# RecordStatusShield.net
KiCad netlist of a schematic drawn in EAGLE
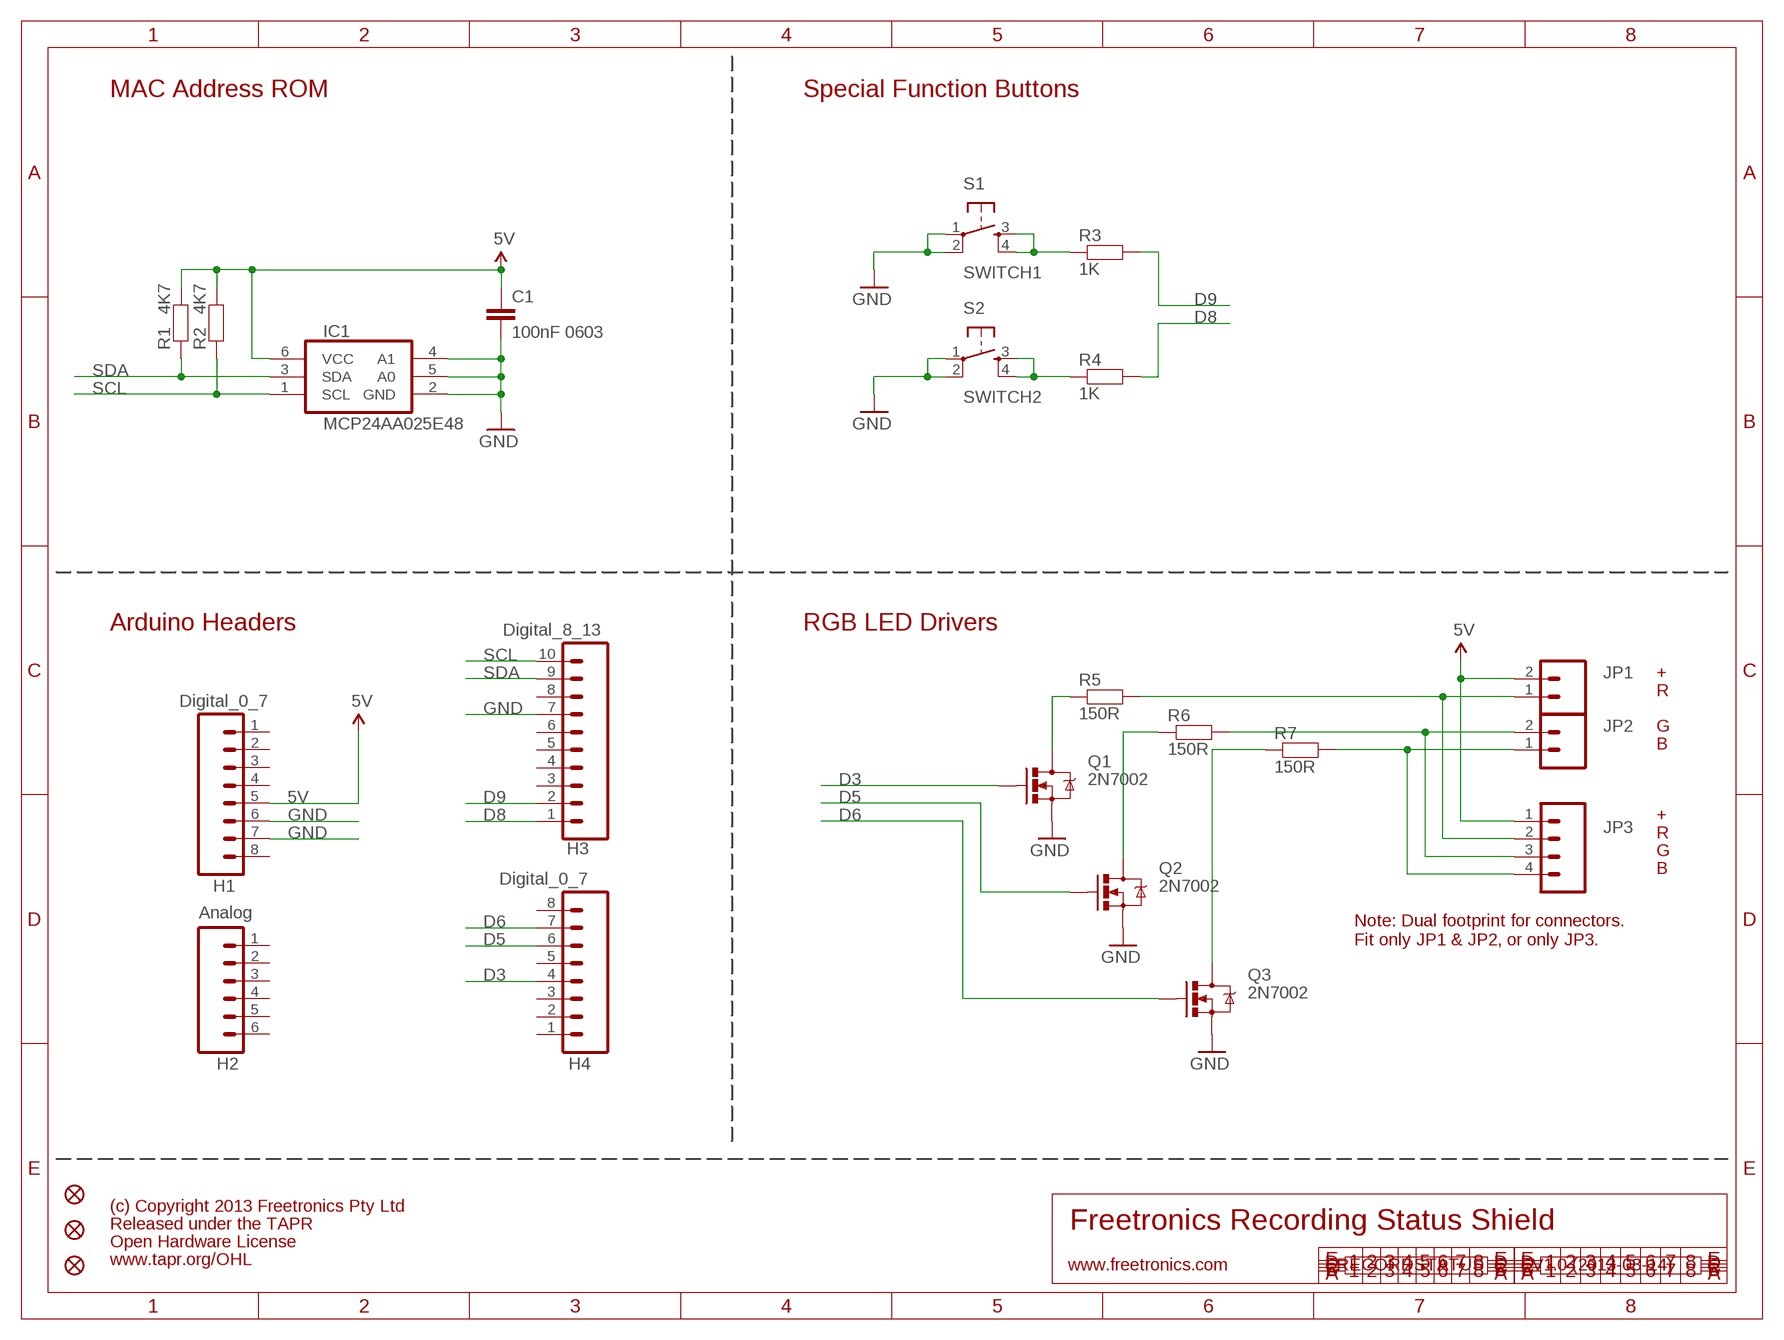
[diagram p0: schematic, sheet 1]

(export (version "E")
  (design (tool "Eeschema 10.0.6"))
  (components
    (comp (ref "C1")
      (value "100nF 0603")
      (footprint "eagle-import:C0603")
      (libsource (lib "eagle-import") (part "C-EUC0603"))
    )
    (comp (ref "FID5")
      (value "FIDUCIAL1X2.5")
      (footprint "eagle-import:FIDUCIAL-1X2.5")
      (libsource (lib "eagle-import") (part "FIDUCIAL1X2.5"))
    )
    (comp (ref "FID6")
      (value "FIDUCIAL1X2.5")
      (footprint "eagle-import:FIDUCIAL-1X2.5")
      (libsource (lib "eagle-import") (part "FIDUCIAL1X2.5"))
    )
    (comp (ref "FID7")
      (value "FIDUCIAL1X2.5")
      (footprint "eagle-import:FIDUCIAL-1X2.5")
      (libsource (lib "eagle-import") (part "FIDUCIAL1X2.5"))
    )
    (comp (ref "H1")
      (value "Digital_0_7")
      (footprint "eagle-import:1X08")
      (libsource (lib "eagle-import") (part "M08"))
    )
    (comp (ref "H2")
      (value "Analog")
      (footprint "eagle-import:1X06")
      (libsource (lib "eagle-import") (part "M06SIP"))
    )
    (comp (ref "H3")
      (value "Digital_8_13")
      (footprint "eagle-import:1X10")
      (libsource (lib "eagle-import") (part "M100.1"))
    )
    (comp (ref "H4")
      (value "Digital_0_7")
      (footprint "eagle-import:1X08")
      (libsource (lib "eagle-import") (part "M08"))
    )
    (comp (ref "IC1")
      (value "MCP24AA025E48")
      (footprint "eagle-import:SOT23-6")
      (libsource (lib "eagle-import") (part "MCP24AA025E48"))
    )
    (comp (ref "JP1")
      (value "M025MM")
      (footprint "eagle-import:SCREWTERMINAL-5MM-2")
      (libsource (lib "eagle-import") (part "M025MM"))
    )
    (comp (ref "JP2")
      (value "M025MM")
      (footprint "eagle-import:SCREWTERMINAL-5MM-2")
      (libsource (lib "eagle-import") (part "M025MM"))
    )
    (comp (ref "JP3")
      (value "M04PTH")
      (footprint "eagle-import:1X04")
      (libsource (lib "eagle-import") (part "M04PTH"))
    )
    (comp (ref "Q1")
      (value "2N7002")
      (footprint "eagle-import:SOT23-3")
      (libsource (lib "eagle-import") (part "MOSFET-NCHANNELSMD"))
    )
    (comp (ref "Q2")
      (value "2N7002")
      (footprint "eagle-import:SOT23-3")
      (libsource (lib "eagle-import") (part "MOSFET-NCHANNELSMD"))
    )
    (comp (ref "Q3")
      (value "2N7002")
      (footprint "eagle-import:SOT23-3")
      (libsource (lib "eagle-import") (part "MOSFET-NCHANNELSMD"))
    )
    (comp (ref "R1")
      (value "4K7")
      (footprint "eagle-import:0603")
      (libsource (lib "eagle-import") (part "RESISTOR0603"))
    )
    (comp (ref "R2")
      (value "4K7")
      (footprint "eagle-import:0603")
      (libsource (lib "eagle-import") (part "RESISTOR0603"))
    )
    (comp (ref "R3")
      (value "1K")
      (footprint "eagle-import:0603")
      (libsource (lib "eagle-import") (part "RESISTOR0603"))
    )
    (comp (ref "R4")
      (value "1K")
      (footprint "eagle-import:0603")
      (libsource (lib "eagle-import") (part "RESISTOR0603"))
    )
    (comp (ref "R5")
      (value "150R")
      (footprint "eagle-import:0603")
      (libsource (lib "eagle-import") (part "RESISTOR0603"))
    )
    (comp (ref "R6")
      (value "150R")
      (footprint "eagle-import:0603")
      (libsource (lib "eagle-import") (part "RESISTOR0603"))
    )
    (comp (ref "R7")
      (value "150R")
      (footprint "eagle-import:0603")
      (libsource (lib "eagle-import") (part "RESISTOR0603"))
    )
    (comp (ref "S1")
      (value "SWITCH1")
      (footprint "eagle-import:TACTILE-PTH")
      (libsource (lib "eagle-import") (part "TAC_SWITCHPTH"))
    )
    (comp (ref "S2")
      (value "SWITCH2")
      (footprint "eagle-import:TACTILE-PTH")
      (libsource (lib "eagle-import") (part "TAC_SWITCHPTH"))
    )
  )
  (nets
    (net (code "1") (name "/D3") (class "Default")
      (node (ref "H4") (pin "4") (pinfunction "4_4") (pintype "passive"))
      (node (ref "Q1") (pin "1") (pinfunction "G_1") (pintype "passive"))
    )
    (net (code "2") (name "/D5") (class "Default")
      (node (ref "H4") (pin "6") (pinfunction "6_6") (pintype "passive"))
      (node (ref "Q2") (pin "1") (pinfunction "G_1") (pintype "passive"))
    )
    (net (code "3") (name "/D6") (class "Default")
      (node (ref "H4") (pin "7") (pinfunction "7_7") (pintype "passive"))
      (node (ref "Q3") (pin "1") (pinfunction "G_1") (pintype "passive"))
    )
    (net (code "4") (name "/D8") (class "Default")
      (node (ref "H3") (pin "1") (pinfunction "1_1") (pintype "passive"))
      (node (ref "R4") (pin "2") (pinfunction "2_2") (pintype "passive"))
    )
    (net (code "5") (name "/D9") (class "Default")
      (node (ref "H3") (pin "2") (pinfunction "2_2") (pintype "passive"))
      (node (ref "R3") (pin "2") (pinfunction "2_2") (pintype "passive"))
    )
    (net (code "6") (name "/SCL") (class "Default")
      (node (ref "H3") (pin "10") (pinfunction "10_10") (pintype "passive"))
      (node (ref "IC1") (pin "1") (pinfunction "SCL_1") (pintype "bidirectional"))
      (node (ref "R2") (pin "1") (pinfunction "1_1") (pintype "passive"))
    )
    (net (code "7") (name "/SDA") (class "Default")
      (node (ref "H3") (pin "9") (pinfunction "9_9") (pintype "passive"))
      (node (ref "IC1") (pin "3") (pinfunction "SDA_3") (pintype "bidirectional"))
      (node (ref "R1") (pin "1") (pinfunction "1_1") (pintype "passive"))
    )
    (net (code "8") (name "5V") (class "Default")
      (node (ref "C1") (pin "1") (pinfunction "1_1") (pintype "passive"))
      (node (ref "H1") (pin "5") (pinfunction "5_5") (pintype "passive"))
      (node (ref "IC1") (pin "6") (pinfunction "VCC_6") (pintype "power_in"))
      (node (ref "JP1") (pin "2") (pinfunction "2_2") (pintype "passive"))
      (node (ref "JP3") (pin "1") (pinfunction "1_1") (pintype "passive"))
      (node (ref "R1") (pin "2") (pinfunction "2_2") (pintype "passive"))
      (node (ref "R2") (pin "2") (pinfunction "2_2") (pintype "passive"))
    )
    (net (code "9") (name "GND") (class "Default")
      (node (ref "C1") (pin "2") (pinfunction "2_2") (pintype "passive"))
      (node (ref "H1") (pin "6") (pinfunction "6_6") (pintype "passive"))
      (node (ref "H1") (pin "7") (pinfunction "7_7") (pintype "passive"))
      (node (ref "H3") (pin "7") (pinfunction "7_7") (pintype "passive"))
      (node (ref "IC1") (pin "2") (pinfunction "GND_2") (pintype "power_in"))
      (node (ref "IC1") (pin "4") (pinfunction "A1_4") (pintype "input"))
      (node (ref "IC1") (pin "5") (pinfunction "A0_5") (pintype "input"))
      (node (ref "Q1") (pin "2") (pinfunction "S_2") (pintype "passive"))
      (node (ref "Q2") (pin "2") (pinfunction "S_2") (pintype "passive"))
      (node (ref "Q3") (pin "2") (pinfunction "S_2") (pintype "passive"))
      (node (ref "S1") (pin "1") (pinfunction "1_1") (pintype "passive"))
      (node (ref "S1") (pin "2") (pinfunction "2_2") (pintype "passive"))
      (node (ref "S2") (pin "1") (pinfunction "1_1") (pintype "passive"))
      (node (ref "S2") (pin "2") (pinfunction "2_2") (pintype "passive"))
    )
    (net (code "10") (name "Net-(JP1-Pad1)") (class "Default")
      (node (ref "JP1") (pin "1") (pinfunction "1_1") (pintype "passive"))
      (node (ref "JP3") (pin "2") (pinfunction "2_2") (pintype "passive"))
      (node (ref "R5") (pin "2") (pinfunction "2_2") (pintype "passive"))
    )
    (net (code "11") (name "Net-(JP2-Pad1)") (class "Default")
      (node (ref "JP2") (pin "1") (pinfunction "1_1") (pintype "passive"))
      (node (ref "JP3") (pin "4") (pinfunction "4_4") (pintype "passive"))
      (node (ref "R7") (pin "2") (pinfunction "2_2") (pintype "passive"))
    )
    (net (code "12") (name "Net-(JP2-Pad2)") (class "Default")
      (node (ref "JP2") (pin "2") (pinfunction "2_2") (pintype "passive"))
      (node (ref "JP3") (pin "3") (pinfunction "3_3") (pintype "passive"))
      (node (ref "R6") (pin "2") (pinfunction "2_2") (pintype "passive"))
    )
    (net (code "13") (name "Net-(Q1-D)") (class "Default")
      (node (ref "Q1") (pin "3") (pinfunction "D_3") (pintype "passive"))
      (node (ref "R5") (pin "1") (pinfunction "1_1") (pintype "passive"))
    )
    (net (code "14") (name "Net-(Q2-D)") (class "Default")
      (node (ref "Q2") (pin "3") (pinfunction "D_3") (pintype "passive"))
      (node (ref "R6") (pin "1") (pinfunction "1_1") (pintype "passive"))
    )
    (net (code "15") (name "Net-(Q3-D)") (class "Default")
      (node (ref "Q3") (pin "3") (pinfunction "D_3") (pintype "passive"))
      (node (ref "R7") (pin "1") (pinfunction "1_1") (pintype "passive"))
    )
    (net (code "16") (name "Net-(R3-Pad1)") (class "Default")
      (node (ref "R3") (pin "1") (pinfunction "1_1") (pintype "passive"))
      (node (ref "S1") (pin "3") (pinfunction "3_3") (pintype "passive"))
      (node (ref "S1") (pin "4") (pinfunction "4_4") (pintype "passive"))
    )
    (net (code "17") (name "Net-(R4-Pad1)") (class "Default")
      (node (ref "R4") (pin "1") (pinfunction "1_1") (pintype "passive"))
      (node (ref "S2") (pin "3") (pinfunction "3_3") (pintype "passive"))
      (node (ref "S2") (pin "4") (pinfunction "4_4") (pintype "passive"))
    )
    (net (code "18") (name "unconnected-(H1-Pad1)") (class "Default")
      (node (ref "H1") (pin "1") (pinfunction "1_1") (pintype "passive"))
    )
    (net (code "19") (name "unconnected-(H1-Pad2)") (class "Default")
      (node (ref "H1") (pin "2") (pinfunction "2_2") (pintype "passive"))
    )
    (net (code "20") (name "unconnected-(H1-Pad3)") (class "Default")
      (node (ref "H1") (pin "3") (pinfunction "3_3") (pintype "passive"))
    )
    (net (code "21") (name "unconnected-(H1-Pad4)") (class "Default")
      (node (ref "H1") (pin "4") (pinfunction "4_4") (pintype "passive"))
    )
    (net (code "22") (name "unconnected-(H1-Pad8)") (class "Default")
      (node (ref "H1") (pin "8") (pinfunction "8_8") (pintype "passive"))
    )
    (net (code "23") (name "unconnected-(H2-Pad1)") (class "Default")
      (node (ref "H2") (pin "1") (pinfunction "1_1") (pintype "passive"))
    )
    (net (code "24") (name "unconnected-(H2-Pad2)") (class "Default")
      (node (ref "H2") (pin "2") (pinfunction "2_2") (pintype "passive"))
    )
    (net (code "25") (name "unconnected-(H2-Pad3)") (class "Default")
      (node (ref "H2") (pin "3") (pinfunction "3_3") (pintype "passive"))
    )
    (net (code "26") (name "unconnected-(H2-Pad4)") (class "Default")
      (node (ref "H2") (pin "4") (pinfunction "4_4") (pintype "passive"))
    )
    (net (code "27") (name "unconnected-(H2-Pad5)") (class "Default")
      (node (ref "H2") (pin "5") (pinfunction "5_5") (pintype "passive"))
    )
    (net (code "28") (name "unconnected-(H2-Pad6)") (class "Default")
      (node (ref "H2") (pin "6") (pinfunction "6_6") (pintype "passive"))
    )
    (net (code "29") (name "unconnected-(H3-Pad3)") (class "Default")
      (node (ref "H3") (pin "3") (pinfunction "3_3") (pintype "passive"))
    )
    (net (code "30") (name "unconnected-(H3-Pad4)") (class "Default")
      (node (ref "H3") (pin "4") (pinfunction "4_4") (pintype "passive"))
    )
    (net (code "31") (name "unconnected-(H3-Pad5)") (class "Default")
      (node (ref "H3") (pin "5") (pinfunction "5_5") (pintype "passive"))
    )
    (net (code "32") (name "unconnected-(H3-Pad6)") (class "Default")
      (node (ref "H3") (pin "6") (pinfunction "6_6") (pintype "passive"))
    )
    (net (code "33") (name "unconnected-(H3-Pad8)") (class "Default")
      (node (ref "H3") (pin "8") (pinfunction "8_8") (pintype "passive"))
    )
    (net (code "34") (name "unconnected-(H4-Pad1)") (class "Default")
      (node (ref "H4") (pin "1") (pinfunction "1_1") (pintype "passive"))
    )
    (net (code "35") (name "unconnected-(H4-Pad2)") (class "Default")
      (node (ref "H4") (pin "2") (pinfunction "2_2") (pintype "passive"))
    )
    (net (code "36") (name "unconnected-(H4-Pad3)") (class "Default")
      (node (ref "H4") (pin "3") (pinfunction "3_3") (pintype "passive"))
    )
    (net (code "37") (name "unconnected-(H4-Pad5)") (class "Default")
      (node (ref "H4") (pin "5") (pinfunction "5_5") (pintype "passive"))
    )
    (net (code "38") (name "unconnected-(H4-Pad8)") (class "Default")
      (node (ref "H4") (pin "8") (pinfunction "8_8") (pintype "passive"))
    )
  )
)
